# cerebro5_11_dbs.net
KiCad netlist of a schematic drawn in EAGLE
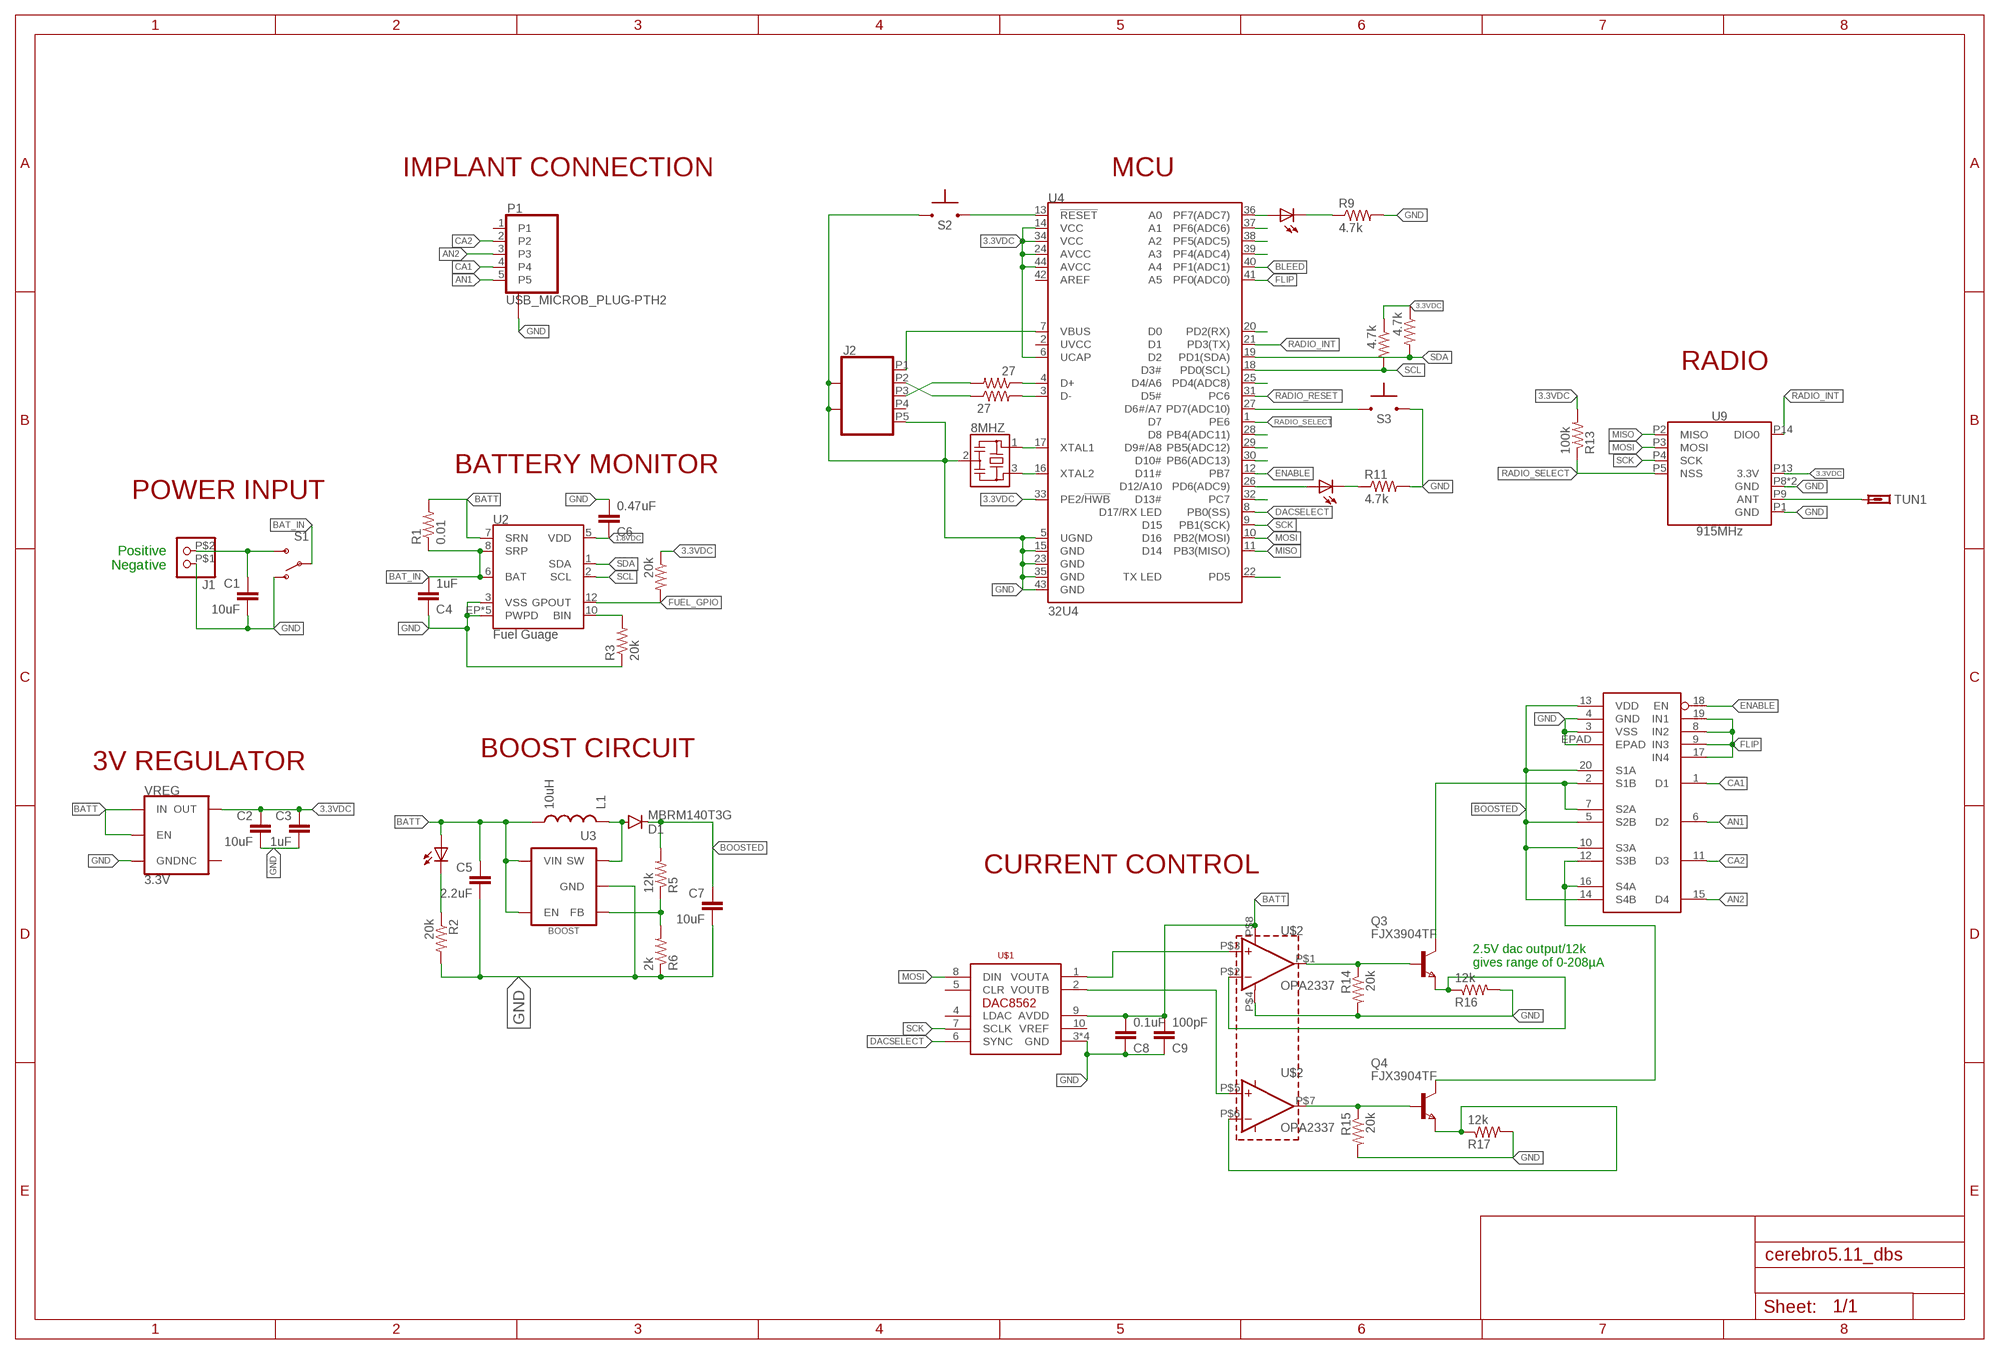
[diagram p0: schematic, sheet 1]

(export (version "E")
  (design (tool "Eeschema 10.0.6"))
  (components
    (comp (ref "8MHZ")
      (value "RESONATOR_CSTCE_V")
      (footprint "eagle-import:CSTCE_V")
      (libsource (lib "eagle-import") (part "RESONATOR_CSTCE_V"))
    )
    (comp (ref "C1")
      (value "10uF")
      (footprint "eagle-import:0805")
      (libsource (lib "eagle-import") (part "10UF-0805-10V-10%"))
    )
    (comp (ref "C2")
      (value "10uF")
      (footprint "eagle-import:0805")
      (libsource (lib "eagle-import") (part "10UF-0805-10V-10%"))
    )
    (comp (ref "C3")
      (value "1uF")
      (footprint "eagle-import:0805")
      (libsource (lib "eagle-import") (part "10UF-0805-10V-10%"))
    )
    (comp (ref "C4")
      (value "1uF")
      (footprint "eagle-import:0805")
      (libsource (lib "eagle-import") (part "10UF-0805-10V-10%"))
    )
    (comp (ref "C5")
      (value "2.2uF")
      (footprint "eagle-import:0805")
      (libsource (lib "eagle-import") (part "2.2UF-0805-25V-(+80/-20%)"))
    )
    (comp (ref "C6")
      (value "0.47uF")
      (footprint "eagle-import:0805")
      (libsource (lib "eagle-import") (part "10UF-0805-10V-10%"))
    )
    (comp (ref "C7")
      (value "10uF")
      (footprint "eagle-import:0805")
      (libsource (lib "eagle-import") (part "10UF-0805-10V-10%"))
    )
    (comp (ref "C8")
      (value "0.1uF")
      (footprint "eagle-import:0805")
      (libsource (lib "eagle-import") (part "10UF-0805-10V-10%"))
    )
    (comp (ref "C9")
      (value "100pF")
      (footprint "eagle-import:0805")
      (libsource (lib "eagle-import") (part "10UF-0805-10V-10%"))
    )
    (comp (ref "D1")
      (value "MBRM140T3G")
      (footprint "eagle-import:POWERMITE")
      (libsource (lib "eagle-import") (part "DIODEPOWERMITE"))
    )
    (comp (ref "J1")
      (value "JST_2PINMICRO")
      (footprint "eagle-import:MICRO_LOCK_2PIN")
      (libsource (lib "eagle-import") (part "JST_2PINMICRO"))
    )
    (comp (ref "J2")
      (value "USB_MICRO_SOCKET_HORZ_REINFORCED")
      (footprint "eagle-import:USB_HORZ_REINFORCED_MICRO")
      (libsource (lib "eagle-import") (part "USB_MICRO_SOCKET_HORZ_REINFORCED"))
    )
    (comp (ref "L1")
      (value "10uH")
      (footprint "eagle-import:1812")
      (libsource (lib "eagle-import") (part "INDUCTORLQH4"))
    )
    (comp (ref "LED1")
      (value "RED")
      (footprint "eagle-import:CHIP-LED0603")
      (libsource (lib "eagle-import") (part "LEDCHIP-LED0603"))
    )
    (comp (ref "LED2")
      (value "YLW")
      (footprint "eagle-import:CHIP-LED0603")
      (libsource (lib "eagle-import") (part "LEDCHIP-LED0603"))
    )
    (comp (ref "LED3")
      (value "YLW")
      (footprint "eagle-import:CHIP-LED0603")
      (libsource (lib "eagle-import") (part "LEDCHIP-LED0603"))
    )
    (comp (ref "P1")
      (value "USB_MICROB_PLUG-PTH2")
      (footprint "eagle-import:MICRO-B-TH")
      (libsource (lib "eagle-import") (part "USB_MICROB_PLUG-PTH2"))
    )
    (comp (ref "Q3")
      (value "FJX3904TF")
      (footprint "eagle-import:SOT323")
      (fields (field (name "MPN") "DSS4160U-7"))
      (libsource (lib "eagle-import") (part "NPNSOT323"))
    )
    (comp (ref "Q4")
      (value "FJX3904TF")
      (footprint "eagle-import:SOT323")
      (fields (field (name "MPN") "DSS4160U-7"))
      (libsource (lib "eagle-import") (part "NPNSOT323"))
    )
    (comp (ref "R1")
      (value "0.01")
      (footprint "eagle-import:1206")
      (libsource (lib "eagle-import") (part "RESISTOR1206"))
    )
    (comp (ref "R2")
      (value "20k")
      (footprint "eagle-import:0603-RES")
      (libsource (lib "eagle-import") (part "RESISTOR0603-RES"))
    )
    (comp (ref "R3")
      (value "20k")
      (footprint "eagle-import:0603-RES")
      (libsource (lib "eagle-import") (part "RESISTOR0603-RES"))
    )
    (comp (ref "R4")
      (value "20k")
      (footprint "eagle-import:0603-RES")
      (libsource (lib "eagle-import") (part "RESISTOR0603-RES"))
    )
    (comp (ref "R5")
      (value "12k")
      (footprint "eagle-import:0805")
      (libsource (lib "eagle-import") (part "RESISTOR0805-RES"))
    )
    (comp (ref "R6")
      (value "2k")
      (footprint "eagle-import:0603-RES")
      (libsource (lib "eagle-import") (part "RESISTOR0603-RES"))
    )
    (comp (ref "R7")
      (value "27")
      (footprint "eagle-import:0603-RES")
      (libsource (lib "eagle-import") (part "RESISTOR0603-RES"))
    )
    (comp (ref "R8")
      (value "27")
      (footprint "eagle-import:0603-RES")
      (libsource (lib "eagle-import") (part "RESISTOR0603-RES"))
    )
    (comp (ref "R9")
      (value "4.7k")
      (footprint "eagle-import:0603-RES")
      (libsource (lib "eagle-import") (part "RESISTOR0603-RES"))
    )
    (comp (ref "R10")
      (value "4.7k")
      (footprint "eagle-import:0603-RES")
      (libsource (lib "eagle-import") (part "RESISTOR0603-RES"))
    )
    (comp (ref "R11")
      (value "4.7k")
      (footprint "eagle-import:0603-RES")
      (libsource (lib "eagle-import") (part "RESISTOR0603-RES"))
    )
    (comp (ref "R12")
      (value "4.7k")
      (footprint "eagle-import:0603-RES")
      (libsource (lib "eagle-import") (part "RESISTOR0603-RES"))
    )
    (comp (ref "R13")
      (value "100k")
      (footprint "eagle-import:0603-RES")
      (libsource (lib "eagle-import") (part "RESISTOR0603-RES"))
    )
    (comp (ref "R14")
      (value "20k")
      (footprint "eagle-import:0603-RES")
      (libsource (lib "eagle-import") (part "RESISTOR0603-RES"))
    )
    (comp (ref "R15")
      (value "20k")
      (footprint "eagle-import:0603-RES")
      (libsource (lib "eagle-import") (part "RESISTOR0603-RES"))
    )
    (comp (ref "R16")
      (value "12k")
      (footprint "eagle-import:0603-RES")
      (libsource (lib "eagle-import") (part "RESISTOR0603-RES"))
    )
    (comp (ref "R17")
      (value "12k")
      (footprint "eagle-import:0603-RES")
      (libsource (lib "eagle-import") (part "RESISTOR0603-RES"))
    )
    (comp (ref "S1")
      (value "SWITCH-SPDTREINFORCED_SMD")
      (footprint "eagle-import:SWITCH-SPDT-SMD-REINFORCED")
      (libsource (lib "eagle-import") (part "SWITCH-SPDTREINFORCED_SMD"))
    )
    (comp (ref "S2")
      (value "SWITCH-MOMENTARY-NO")
      (footprint "eagle-import:SWITCH_MOMENTARY_XS")
      (libsource (lib "eagle-import") (part "SWITCH-MOMENTARY-NO"))
    )
    (comp (ref "S3")
      (value "SWITCH-MOMENTARY-NO")
      (footprint "eagle-import:SWITCH_MOMENTARY_XS")
      (libsource (lib "eagle-import") (part "SWITCH-MOMENTARY-NO"))
    )
    (comp (ref "TUN1")
      (value "ANTENNA")
      (footprint "eagle-import:1X01")
      (libsource (lib "eagle-import") (part "ANTENNA"))
    )
    (comp (ref "U$1")
      (value "DAC8562")
      (footprint "eagle-import:WSON-10")
      (libsource (lib "eagle-import") (part "DAC8562"))
    )
    (comp (ref "U$2")
      (value "OPA2337")
      (footprint "eagle-import:SOT23-8")
      (libsource (lib "eagle-import") (part "OPA2337"))
    )
    (comp (ref "U$3")
      (value "ADG1434")
      (footprint "eagle-import:LFCSP_5X5")
      (libsource (lib "eagle-import") (part "ADG1434"))
    )
    (comp (ref "U2")
      (value "Fuel Guage")
      (footprint "eagle-import:PDSO-N12")
      (libsource (lib "eagle-import") (part "BQ27441-G1"))
    )
    (comp (ref "U3")
      (value "BOOST")
      (footprint "eagle-import:SOT23-5")
      (libsource (lib "eagle-import") (part "BOOST_CONVERTER"))
    )
    (comp (ref "U4")
      (value "32U4")
      (footprint "eagle-import:QFN-44-NOPAD")
      (libsource (lib "eagle-import") (part "ATMEGA32U4QFN2"))
    )
    (comp (ref "U9")
      (value "915MHz")
      (footprint "eagle-import:RFM69HCW-XXXS2")
      (libsource (lib "eagle-import") (part "RFM69HCW-915"))
    )
    (comp (ref "VREG")
      (value "3.3V")
      (footprint "eagle-import:SOT23-5")
      (libsource (lib "eagle-import") (part "V_REG_AP2112K-3.3V"))
    )
  )
  (nets
    (net (code "1") (name "1.8VDC") (class "Default")
      (node (ref "C6") (pin "1") (pinfunction "1_1") (pintype "passive"))
      (node (ref "U2") (pin "5") (pinfunction "VDD_5") (pintype "bidirectional"))
    )
    (net (code "2") (name "3.3VDC") (class "Default")
      (node (ref "C2") (pin "1") (pinfunction "1_1") (pintype "passive"))
      (node (ref "C3") (pin "1") (pinfunction "1_1") (pintype "passive"))
      (node (ref "R10") (pin "1") (pinfunction "1_1") (pintype "passive"))
      (node (ref "R12") (pin "1") (pinfunction "1_1") (pintype "passive"))
      (node (ref "R13") (pin "2") (pinfunction "2_2") (pintype "passive"))
      (node (ref "R4") (pin "1") (pinfunction "1_1") (pintype "passive"))
      (node (ref "U4") (pin "14") (pinfunction "VCC_14") (pintype "bidirectional"))
      (node (ref "U4") (pin "24") (pinfunction "AVCC_24") (pintype "bidirectional"))
      (node (ref "U4") (pin "33") (pinfunction "PE2/~{HWB}_33") (pintype "bidirectional"))
      (node (ref "U4") (pin "34") (pinfunction "VCC_34") (pintype "bidirectional"))
      (node (ref "U4") (pin "44") (pinfunction "AVCC_44") (pintype "bidirectional"))
      (node (ref "U4") (pin "6") (pinfunction "UCAP_6") (pintype "bidirectional"))
      (node (ref "U9") (pin "P13") (pinfunction "3.3V_P13") (pintype "power_in"))
      (node (ref "VREG") (pin "5") (pinfunction "OUT_5") (pintype "passive"))
    )
    (net (code "3") (name "AN1") (class "Default")
      (node (ref "P1") (pin "5") (pinfunction "P5_5") (pintype "bidirectional"))
      (node (ref "U$3") (pin "6") (pinfunction "D2_6") (pintype "bidirectional"))
    )
    (net (code "4") (name "AN2") (class "Default")
      (node (ref "P1") (pin "3") (pinfunction "P3_3") (pintype "bidirectional"))
      (node (ref "U$3") (pin "15") (pinfunction "D4_15") (pintype "bidirectional"))
    )
    (net (code "5") (name "BATT") (class "Default")
      (node (ref "C5") (pin "1") (pinfunction "1_1") (pintype "passive"))
      (node (ref "C8") (pin "2") (pinfunction "2_2") (pintype "passive"))
      (node (ref "C9") (pin "2") (pinfunction "2_2") (pintype "passive"))
      (node (ref "L1") (pin "P$2") (pinfunction "2_P$2") (pintype "passive"))
      (node (ref "L1") (pin "P$4") (pinfunction "2_P$4") (pintype "passive"))
      (node (ref "LED1") (pin "A") (pinfunction "A_A") (pintype "passive"))
      (node (ref "R1") (pin "2") (pinfunction "2_2") (pintype "passive"))
      (node (ref "U$1") (pin "9") (pinfunction "AVDD_9") (pintype "input"))
      (node (ref "U$2") (pin "P$8") (pinfunction "V+_P$8") (pintype "power_in"))
      (node (ref "U2") (pin "7") (pinfunction "SRN_7") (pintype "bidirectional"))
      (node (ref "U3") (pin "4") (pinfunction "EN_4") (pintype "input"))
      (node (ref "U3") (pin "5") (pinfunction "VIN_5") (pintype "passive"))
      (node (ref "VREG") (pin "1") (pinfunction "IN_1") (pintype "input"))
      (node (ref "VREG") (pin "3") (pinfunction "EN_3") (pintype "input"))
    )
    (net (code "6") (name "BAT_IN") (class "Default")
      (node (ref "C4") (pin "2") (pinfunction "2_2") (pintype "passive"))
      (node (ref "R1") (pin "1") (pinfunction "1_1") (pintype "passive"))
      (node (ref "S1") (pin "2") (pinfunction "P_2") (pintype "passive"))
      (node (ref "U2") (pin "6") (pinfunction "BAT_6") (pintype "bidirectional"))
      (node (ref "U2") (pin "8") (pinfunction "SRP_8") (pintype "bidirectional"))
    )
    (net (code "7") (name "BLEED") (class "Default")
      (node (ref "U4") (pin "40") (pinfunction "PF1(ADC1)_40") (pintype "bidirectional"))
    )
    (net (code "8") (name "BOOSTED") (class "Default")
      (node (ref "C7") (pin "1") (pinfunction "1_1") (pintype "passive"))
      (node (ref "D1") (pin "CATHODE") (pinfunction "C_CATHODE") (pintype "passive"))
      (node (ref "R5") (pin "2") (pinfunction "2_2") (pintype "passive"))
      (node (ref "U$3") (pin "10") (pinfunction "S3A_10") (pintype "bidirectional"))
      (node (ref "U$3") (pin "13") (pinfunction "VDD_13") (pintype "power_in"))
      (node (ref "U$3") (pin "14") (pinfunction "S4B_14") (pintype "bidirectional"))
      (node (ref "U$3") (pin "20") (pinfunction "S1A_20") (pintype "bidirectional"))
      (node (ref "U$3") (pin "5") (pinfunction "S2B_5") (pintype "bidirectional"))
    )
    (net (code "9") (name "CA1") (class "Default")
      (node (ref "P1") (pin "4") (pinfunction "P4_4") (pintype "bidirectional"))
      (node (ref "U$3") (pin "1") (pinfunction "D1_1") (pintype "bidirectional"))
    )
    (net (code "10") (name "CA2") (class "Default")
      (node (ref "P1") (pin "2") (pinfunction "P2_2") (pintype "bidirectional"))
      (node (ref "U$3") (pin "11") (pinfunction "D3_11") (pintype "bidirectional"))
    )
    (net (code "11") (name "DACSELECT") (class "Default")
      (node (ref "U$1") (pin "6") (pinfunction "SYNC_6") (pintype "input"))
      (node (ref "U4") (pin "8") (pinfunction "PB0(SS)_8") (pintype "bidirectional"))
    )
    (net (code "12") (name "ENABLE") (class "Default")
      (node (ref "U$3") (pin "18") (pinfunction "EN_18") (pintype "input"))
      (node (ref "U4") (pin "12") (pinfunction "PB7_12") (pintype "bidirectional"))
    )
    (net (code "13") (name "FLIP") (class "Default")
      (node (ref "U$3") (pin "17") (pinfunction "IN4_17") (pintype "input"))
      (node (ref "U$3") (pin "19") (pinfunction "IN1_19") (pintype "input"))
      (node (ref "U$3") (pin "8") (pinfunction "IN2_8") (pintype "input"))
      (node (ref "U$3") (pin "9") (pinfunction "IN3_9") (pintype "input"))
      (node (ref "U4") (pin "41") (pinfunction "PF0(ADC0)_41") (pintype "bidirectional"))
    )
    (net (code "14") (name "FUEL_GPIO") (class "Default")
      (node (ref "R4") (pin "2") (pinfunction "2_2") (pintype "passive"))
      (node (ref "U2") (pin "12") (pinfunction "GPOUT_12") (pintype "bidirectional"))
    )
    (net (code "15") (name "GND") (class "Default")
      (node (ref "8MHZ") (pin "2") (pinfunction "2_2") (pintype "passive"))
      (node (ref "C1") (pin "2") (pinfunction "2_2") (pintype "passive"))
      (node (ref "C2") (pin "2") (pinfunction "2_2") (pintype "passive"))
      (node (ref "C3") (pin "2") (pinfunction "2_2") (pintype "passive"))
      (node (ref "C4") (pin "1") (pinfunction "1_1") (pintype "passive"))
      (node (ref "C5") (pin "2") (pinfunction "2_2") (pintype "passive"))
      (node (ref "C6") (pin "2") (pinfunction "2_2") (pintype "passive"))
      (node (ref "C7") (pin "2") (pinfunction "2_2") (pintype "passive"))
      (node (ref "C8") (pin "1") (pinfunction "1_1") (pintype "passive"))
      (node (ref "C9") (pin "1") (pinfunction "1_1") (pintype "passive"))
      (node (ref "J1") (pin "P$1") (pinfunction "1_P$1") (pintype "passive"))
      (node (ref "J2") (pin "G1") (pinfunction "P$1_G1") (pintype "bidirectional"))
      (node (ref "J2") (pin "G2") (pinfunction "P$1_G2") (pintype "bidirectional"))
      (node (ref "J2") (pin "P$1") (pinfunction "P$2_P$1") (pintype "bidirectional"))
      (node (ref "J2") (pin "P$2") (pinfunction "P$2_P$2") (pintype "bidirectional"))
      (node (ref "J2") (pin "P5") (pinfunction "P5_P5") (pintype "bidirectional"))
      (node (ref "P1") (pin "P$1") (pinfunction "GND_PINS_P$1") (pintype "bidirectional"))
      (node (ref "P1") (pin "P$2") (pinfunction "GND_PINS_P$2") (pintype "bidirectional"))
      (node (ref "R11") (pin "2") (pinfunction "2_2") (pintype "passive"))
      (node (ref "R14") (pin "2") (pinfunction "2_2") (pintype "passive"))
      (node (ref "R15") (pin "2") (pinfunction "2_2") (pintype "passive"))
      (node (ref "R16") (pin "2") (pinfunction "2_2") (pintype "passive"))
      (node (ref "R17") (pin "2") (pinfunction "2_2") (pintype "passive"))
      (node (ref "R2") (pin "2") (pinfunction "2_2") (pintype "passive"))
      (node (ref "R3") (pin "1") (pinfunction "1_1") (pintype "passive"))
      (node (ref "R6") (pin "1") (pinfunction "1_1") (pintype "passive"))
      (node (ref "R9") (pin "2") (pinfunction "2_2") (pintype "passive"))
      (node (ref "S1") (pin "1") (pinfunction "O_1") (pintype "passive"))
      (node (ref "S2") (pin "P$1") (pinfunction "1_P$1") (pintype "bidirectional"))
      (node (ref "S3") (pin "P$2") (pinfunction "2_P$2") (pintype "bidirectional"))
      (node (ref "U$1") (pin "3") (pinfunction "GND_3") (pintype "input"))
      (node (ref "U$1") (pin "G1") (pinfunction "GND_G1") (pintype "input"))
      (node (ref "U$1") (pin "G2") (pinfunction "GND_G2") (pintype "input"))
      (node (ref "U$1") (pin "G3") (pinfunction "GND_G3") (pintype "input"))
      (node (ref "U$2") (pin "P$4") (pinfunction "V-_P$4") (pintype "power_in"))
      (node (ref "U$3") (pin "3") (pinfunction "VSS_3") (pintype "power_in"))
      (node (ref "U$3") (pin "4") (pinfunction "GND_4") (pintype "power_in"))
      (node (ref "U$3") (pin "EPAD") (pinfunction "EPAD_EPAD") (pintype "bidirectional"))
      (node (ref "U2") (pin "3") (pinfunction "VSS_3") (pintype "bidirectional"))
      (node (ref "U2") (pin "EP") (pinfunction "PWPD_EP") (pintype "bidirectional"))
      (node (ref "U2") (pin "EP1") (pinfunction "PWPD_EP1") (pintype "bidirectional"))
      (node (ref "U2") (pin "EP2") (pinfunction "PWPD_EP2") (pintype "bidirectional"))
      (node (ref "U2") (pin "EP3") (pinfunction "PWPD_EP3") (pintype "bidirectional"))
      (node (ref "U2") (pin "EP4") (pinfunction "PWPD_EP4") (pintype "bidirectional"))
      (node (ref "U3") (pin "2") (pinfunction "GND_2") (pintype "input"))
      (node (ref "U4") (pin "15") (pinfunction "GND_15") (pintype "bidirectional"))
      (node (ref "U4") (pin "23") (pinfunction "GND_23") (pintype "bidirectional"))
      (node (ref "U4") (pin "35") (pinfunction "GND_35") (pintype "bidirectional"))
      (node (ref "U4") (pin "43") (pinfunction "GND_43") (pintype "bidirectional"))
      (node (ref "U4") (pin "5") (pinfunction "UGND_5") (pintype "bidirectional"))
      (node (ref "U9") (pin "P1") (pinfunction "GND_P1") (pintype "power_in"))
      (node (ref "U9") (pin "P10") (pinfunction "GND_P10") (pintype "power_in"))
      (node (ref "U9") (pin "P8") (pinfunction "GND_P8") (pintype "power_in"))
      (node (ref "VREG") (pin "2") (pinfunction "GND_2") (pintype "input"))
    )
    (net (code "16") (name "MISO") (class "Default")
      (node (ref "U4") (pin "11") (pinfunction "PB3(MISO)_11") (pintype "bidirectional"))
      (node (ref "U9") (pin "P2") (pinfunction "MISO_P2") (pintype "bidirectional"))
    )
    (net (code "17") (name "MOSI") (class "Default")
      (node (ref "U$1") (pin "8") (pinfunction "DIN_8") (pintype "input"))
      (node (ref "U4") (pin "10") (pinfunction "PB2(MOSI)_10") (pintype "bidirectional"))
      (node (ref "U9") (pin "P3") (pinfunction "MOSI_P3") (pintype "input"))
    )
    (net (code "18") (name "Net-(D1-A)") (class "Default")
      (node (ref "D1") (pin "ANODE") (pinfunction "A_ANODE") (pintype "passive"))
      (node (ref "L1") (pin "P$1") (pinfunction "1_P$1") (pintype "passive"))
      (node (ref "L1") (pin "P$3") (pinfunction "1_P$3") (pintype "passive"))
      (node (ref "U3") (pin "1") (pinfunction "SW_1") (pintype "input"))
    )
    (net (code "19") (name "Net-(J1-2)") (class "Default")
      (node (ref "C1") (pin "1") (pinfunction "1_1") (pintype "passive"))
      (node (ref "J1") (pin "P$2") (pinfunction "2_P$2") (pintype "passive"))
      (node (ref "S1") (pin "3") (pinfunction "S_3") (pintype "passive"))
    )
    (net (code "20") (name "Net-(J2-PadP2)") (class "Default")
      (node (ref "J2") (pin "P2") (pinfunction "P2_P2") (pintype "bidirectional"))
      (node (ref "R8") (pin "1") (pinfunction "1_1") (pintype "passive"))
    )
    (net (code "21") (name "Net-(J2-PadP3)") (class "Default")
      (node (ref "J2") (pin "P3") (pinfunction "P3_P3") (pintype "bidirectional"))
      (node (ref "R7") (pin "2") (pinfunction "2_2") (pintype "passive"))
    )
    (net (code "22") (name "Net-(LED1-PadC)") (class "Default")
      (node (ref "LED1") (pin "C") (pinfunction "C_C") (pintype "passive"))
      (node (ref "R2") (pin "1") (pinfunction "1_1") (pintype "passive"))
    )
    (net (code "23") (name "Net-(LED2-PadC)") (class "Default")
      (node (ref "LED2") (pin "C") (pinfunction "C_C") (pintype "passive"))
      (node (ref "R9") (pin "1") (pinfunction "1_1") (pintype "passive"))
    )
    (net (code "24") (name "Net-(LED3-PadC)") (class "Default")
      (node (ref "LED3") (pin "C") (pinfunction "C_C") (pintype "passive"))
      (node (ref "R11") (pin "1") (pinfunction "1_1") (pintype "passive"))
    )
    (net (code "25") (name "Net-(Q3-B)") (class "Default")
      (node (ref "Q3") (pin "2") (pinfunction "B_2") (pintype "passive"))
      (node (ref "R14") (pin "1") (pinfunction "1_1") (pintype "passive"))
      (node (ref "U$2") (pin "P$1") (pinfunction "OUTA_P$1") (pintype "output"))
    )
    (net (code "26") (name "Net-(Q3-C)") (class "Default")
      (node (ref "Q3") (pin "1") (pinfunction "C_1") (pintype "passive"))
      (node (ref "U$3") (pin "2") (pinfunction "S1B_2") (pintype "bidirectional"))
      (node (ref "U$3") (pin "7") (pinfunction "S2A_7") (pintype "bidirectional"))
    )
    (net (code "27") (name "Net-(Q3-E)") (class "Default")
      (node (ref "Q3") (pin "3") (pinfunction "E_3") (pintype "passive"))
      (node (ref "R16") (pin "1") (pinfunction "1_1") (pintype "passive"))
      (node (ref "U$2") (pin "P$2") (pinfunction "INA-_P$2") (pintype "input"))
    )
    (net (code "28") (name "Net-(Q4-B)") (class "Default")
      (node (ref "Q4") (pin "2") (pinfunction "B_2") (pintype "passive"))
      (node (ref "R15") (pin "1") (pinfunction "1_1") (pintype "passive"))
      (node (ref "U$2") (pin "P$7") (pinfunction "OUTB_P$7") (pintype "output"))
    )
    (net (code "29") (name "Net-(Q4-C)") (class "Default")
      (node (ref "Q4") (pin "1") (pinfunction "C_1") (pintype "passive"))
      (node (ref "U$3") (pin "12") (pinfunction "S3B_12") (pintype "bidirectional"))
      (node (ref "U$3") (pin "16") (pinfunction "S4A_16") (pintype "bidirectional"))
    )
    (net (code "30") (name "Net-(Q4-E)") (class "Default")
      (node (ref "Q4") (pin "3") (pinfunction "E_3") (pintype "passive"))
      (node (ref "R17") (pin "1") (pinfunction "1_1") (pintype "passive"))
      (node (ref "U$2") (pin "P$6") (pinfunction "INB-_P$6") (pintype "input"))
    )
    (net (code "31") (name "Net-(S2-2)") (class "Default")
      (node (ref "S2") (pin "P$2") (pinfunction "2_P$2") (pintype "bidirectional"))
      (node (ref "U4") (pin "13") (pinfunction "~{RESET}_13") (pintype "bidirectional"))
    )
    (net (code "32") (name "Net-(S3-1)") (class "Default")
      (node (ref "S3") (pin "P$1") (pinfunction "1_P$1") (pintype "bidirectional"))
      (node (ref "U4") (pin "27") (pinfunction "PD7(ADC10)_27") (pintype "bidirectional"))
    )
    (net (code "33") (name "Net-(U$1-VOUTA)") (class "Default")
      (node (ref "U$1") (pin "1") (pinfunction "VOUTA_1") (pintype "output"))
      (node (ref "U$2") (pin "P$3") (pinfunction "INA+_P$3") (pintype "input"))
    )
    (net (code "34") (name "Net-(U$1-VOUTB)") (class "Default")
      (node (ref "U$1") (pin "2") (pinfunction "VOUTB_2") (pintype "output"))
      (node (ref "U$2") (pin "P$5") (pinfunction "INB+_P$5") (pintype "input"))
    )
    (net (code "35") (name "Net-(U2-BIN)") (class "Default")
      (node (ref "R3") (pin "2") (pinfunction "2_2") (pintype "passive"))
      (node (ref "U2") (pin "10") (pinfunction "BIN_10") (pintype "bidirectional"))
    )
    (net (code "36") (name "Net-(U3-FB)") (class "Default")
      (node (ref "R5") (pin "1") (pinfunction "1_1") (pintype "passive"))
      (node (ref "R6") (pin "2") (pinfunction "2_2") (pintype "passive"))
      (node (ref "U3") (pin "3") (pinfunction "FB_3") (pintype "input"))
    )
    (net (code "37") (name "Net-(U4-D+)") (class "Default")
      (node (ref "R7") (pin "1") (pinfunction "1_1") (pintype "passive"))
      (node (ref "U4") (pin "4") (pinfunction "D+_4") (pintype "bidirectional"))
    )
    (net (code "38") (name "Net-(U4-D-)") (class "Default")
      (node (ref "R8") (pin "2") (pinfunction "2_2") (pintype "passive"))
      (node (ref "U4") (pin "3") (pinfunction "D-_3") (pintype "bidirectional"))
    )
    (net (code "39") (name "Net-(U4-PD6(ADC9))") (class "Default")
      (node (ref "LED3") (pin "A") (pinfunction "A_A") (pintype "passive"))
      (node (ref "U4") (pin "26") (pinfunction "PD6(ADC9)_26") (pintype "bidirectional"))
    )
    (net (code "40") (name "Net-(U4-PF7(ADC7))") (class "Default")
      (node (ref "LED2") (pin "A") (pinfunction "A_A") (pintype "passive"))
      (node (ref "U4") (pin "36") (pinfunction "PF7(ADC7)_36") (pintype "bidirectional"))
    )
    (net (code "41") (name "Net-(U4-VBUS)") (class "Default")
      (node (ref "J2") (pin "P1") (pinfunction "P1_P1") (pintype "bidirectional"))
      (node (ref "U4") (pin "7") (pinfunction "VBUS_7") (pintype "bidirectional"))
    )
    (net (code "42") (name "Net-(U4-XTAL1)") (class "Default")
      (node (ref "8MHZ") (pin "1") (pinfunction "1_1") (pintype "passive"))
      (node (ref "U4") (pin "17") (pinfunction "XTAL1_17") (pintype "bidirectional"))
    )
    (net (code "43") (name "Net-(U4-XTAL2)") (class "Default")
      (node (ref "8MHZ") (pin "3") (pinfunction "3_3") (pintype "passive"))
      (node (ref "U4") (pin "16") (pinfunction "XTAL2_16") (pintype "bidirectional"))
    )
    (net (code "44") (name "Net-(U9-ANT)") (class "Default")
      (node (ref "TUN1") (pin "1") (pinfunction "1_1") (pintype "passive"))
      (node (ref "U9") (pin "P9") (pinfunction "ANT_P9") (pintype "passive"))
    )
    (net (code "45") (name "RADIO_INT") (class "Default")
      (node (ref "U4") (pin "21") (pinfunction "PD3(TX)_21") (pintype "bidirectional"))
      (node (ref "U9") (pin "P14") (pinfunction "DIO0_P14") (pintype "bidirectional"))
    )
    (net (code "46") (name "RADIO_RESET") (class "Default")
      (node (ref "U4") (pin "31") (pinfunction "PC6_31") (pintype "bidirectional"))
    )
    (net (code "47") (name "RADIO_SELECT") (class "Default")
      (node (ref "R13") (pin "1") (pinfunction "1_1") (pintype "passive"))
      (node (ref "U4") (pin "1") (pinfunction "PE6_1") (pintype "bidirectional"))
      (node (ref "U9") (pin "P5") (pinfunction "NSS_P5") (pintype "input"))
    )
    (net (code "48") (name "SCK") (class "Default")
      (node (ref "U$1") (pin "7") (pinfunction "SCLK_7") (pintype "input"))
      (node (ref "U4") (pin "9") (pinfunction "PB1(SCK)_9") (pintype "bidirectional"))
      (node (ref "U9") (pin "P4") (pinfunction "SCK_P4") (pintype "input"))
    )
    (net (code "49") (name "SCL") (class "Default")
      (node (ref "R10") (pin "2") (pinfunction "2_2") (pintype "passive"))
      (node (ref "U2") (pin "2") (pinfunction "SCL_2") (pintype "bidirectional"))
      (node (ref "U4") (pin "18") (pinfunction "PD0(SCL)_18") (pintype "bidirectional"))
    )
    (net (code "50") (name "SDA") (class "Default")
      (node (ref "R12") (pin "2") (pinfunction "2_2") (pintype "passive"))
      (node (ref "U2") (pin "1") (pinfunction "SDA_1") (pintype "bidirectional"))
      (node (ref "U4") (pin "19") (pinfunction "PD1(SDA)_19") (pintype "bidirectional"))
    )
    (net (code "51") (name "unconnected-(J2-PadP4)") (class "Default")
      (node (ref "J2") (pin "P4") (pinfunction "P4_P4") (pintype "bidirectional"))
    )
    (net (code "52") (name "unconnected-(P1-P1-Pad1)") (class "Default")
      (node (ref "P1") (pin "1") (pinfunction "P1_1") (pintype "bidirectional"))
    )
    (net (code "53") (name "unconnected-(U$1-CLR-Pad5)") (class "Default")
      (node (ref "U$1") (pin "5") (pinfunction "CLR_5") (pintype "input"))
    )
    (net (code "54") (name "unconnected-(U$1-LDAC-Pad4)") (class "Default")
      (node (ref "U$1") (pin "4") (pinfunction "LDAC_4") (pintype "input"))
    )
    (net (code "55") (name "unconnected-(U$1-VREF-Pad10)") (class "Default")
      (node (ref "U$1") (pin "10") (pinfunction "VREF_10") (pintype "bidirectional"))
    )
    (net (code "56") (name "unconnected-(U4-AREF-Pad42)") (class "Default")
      (node (ref "U4") (pin "42") (pinfunction "AREF_42") (pintype "bidirectional"))
    )
    (net (code "57") (name "unconnected-(U4-PB4(ADC11)-Pad28)") (class "Default")
      (node (ref "U4") (pin "28") (pinfunction "PB4(ADC11)_28") (pintype "bidirectional"))
    )
    (net (code "58") (name "unconnected-(U4-PB5(ADC12)-Pad29)") (class "Default")
      (node (ref "U4") (pin "29") (pinfunction "PB5(ADC12)_29") (pintype "bidirectional"))
    )
    (net (code "59") (name "unconnected-(U4-PB6(ADC13)-Pad30)") (class "Default")
      (node (ref "U4") (pin "30") (pinfunction "PB6(ADC13)_30") (pintype "bidirectional"))
    )
    (net (code "60") (name "unconnected-(U4-PC7-Pad32)") (class "Default")
      (node (ref "U4") (pin "32") (pinfunction "PC7_32") (pintype "bidirectional"))
    )
    (net (code "61") (name "unconnected-(U4-PD2(RX)-Pad20)") (class "Default")
      (node (ref "U4") (pin "20") (pinfunction "PD2(RX)_20") (pintype "bidirectional"))
    )
    (net (code "62") (name "unconnected-(U4-PD4(ADC8)-Pad25)") (class "Default")
      (node (ref "U4") (pin "25") (pinfunction "PD4(ADC8)_25") (pintype "bidirectional"))
    )
    (net (code "63") (name "unconnected-(U4-PD5-Pad22)") (class "Default")
      (node (ref "U4") (pin "22") (pinfunction "PD5_22") (pintype "bidirectional"))
    )
    (net (code "64") (name "unconnected-(U4-PF4(ADC4)-Pad39)") (class "Default")
      (node (ref "U4") (pin "39") (pinfunction "PF4(ADC4)_39") (pintype "bidirectional"))
    )
    (net (code "65") (name "unconnected-(U4-PF5(ADC5)-Pad38)") (class "Default")
      (node (ref "U4") (pin "38") (pinfunction "PF5(ADC5)_38") (pintype "bidirectional"))
    )
    (net (code "66") (name "unconnected-(U4-PF6(ADC6)-Pad37)") (class "Default")
      (node (ref "U4") (pin "37") (pinfunction "PF6(ADC6)_37") (pintype "bidirectional"))
    )
    (net (code "67") (name "unconnected-(U4-UVCC-Pad2)") (class "Default")
      (node (ref "U4") (pin "2") (pinfunction "UVCC_2") (pintype "bidirectional"))
    )
    (net (code "68") (name "unconnected-(VREG-NC-Pad4)") (class "Default")
      (node (ref "VREG") (pin "4") (pinfunction "NC_4") (pintype "no_connect"))
    )
  )
)
